# ALIM_MOSFET_1.net
KiCad netlist of a schematic drawn in Altium Designer
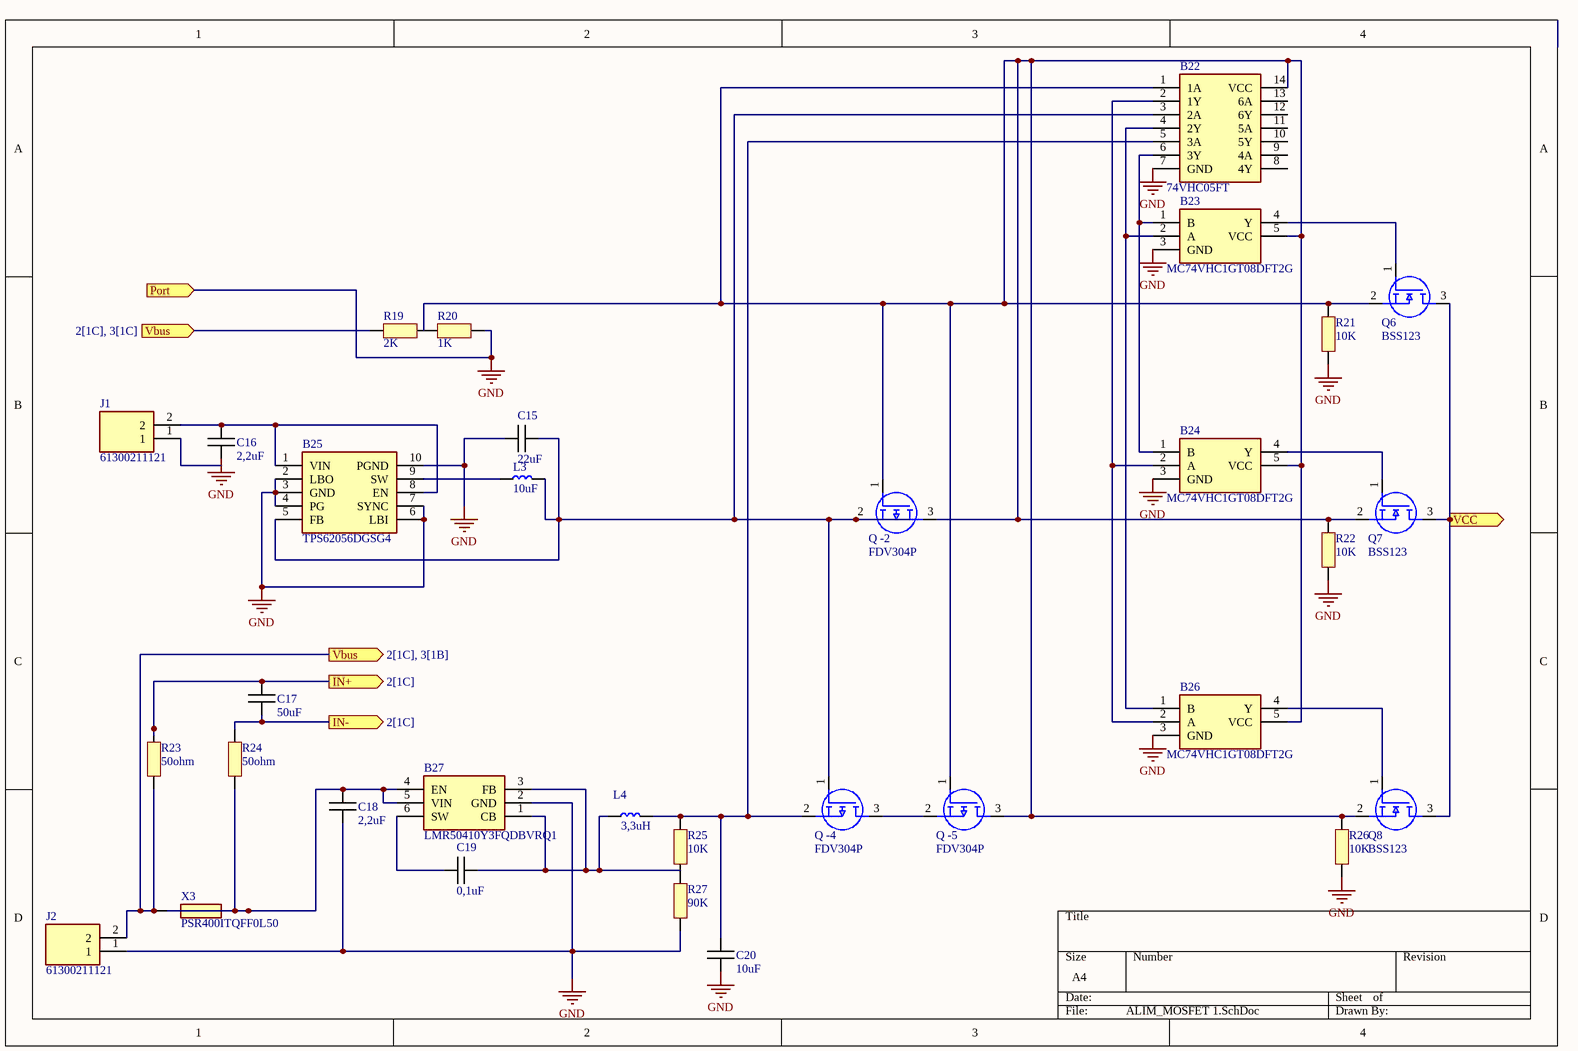
[diagram p0: ALIM_MOSFET 1.SchDoc]

(export (version "E")
  (design (tool "Eeschema 10.0.6"))
  (components
    (comp (ref "B22")
      (value "74VHC05FT")
      (footprint "SOP65P640X120-14N")
      (description "Logic Gates CMOS LOGIC IC INVERTER")
      (fields (field (name "MOUSER PART NUMBER") "757-74VHC05FT"))
      (libsource (lib "SCHLibrary") (part "74VHC05FT"))
    )
    (comp (ref "B23")
      (value "MC74VHC1GT08DFT2G")
      (footprint "SOT65P210X110-5N")
      (description "Single 2-Input AND Gate, TTL Level")
      (libsource (lib "SCHLibrary") (part "MC74VHC1GT08DFT2G"))
    )
    (comp (ref "B24")
      (value "MC74VHC1GT08DFT2G")
      (footprint "SOT65P210X110-5N")
      (description "Single 2-Input AND Gate, TTL Level")
      (libsource (lib "SCHLibrary") (part "MC74VHC1GT08DFT2G"))
    )
    (comp (ref "B25")
      (value "TPS62056DGSG4")
      (footprint "SOP50P490X110-10N")
      (fields (field (name "MOUSER PART NUMBER") "595-TPS62056DGSG4"))
      (libsource (lib "SCHLibrary") (part "TPS62056DGSG4"))
    )
    (comp (ref "B26")
      (value "MC74VHC1GT08DFT2G")
      (footprint "SOT65P210X110-5N")
      (description "Single 2-Input AND Gate, TTL Level")
      (libsource (lib "SCHLibrary") (part "MC74VHC1GT08DFT2G"))
    )
    (comp (ref "B27")
      (value "LMR50410Y3FQDBVRQ1")
      (footprint "SOT95P280X145-6N")
      (fields (field (name "MOUSER PART NUMBER") "595-R50410Y3FQDBVRQ1"))
      (libsource (lib "SCHLibrary") (part "LMR50410Y3FQDBVRQ1"))
    )
    (comp (ref "C15")
      (value "22uF")
      (footprint "CAPC1005X06N")
      (libsource (lib "SCHLibrary") (part "Capacitor"))
    )
    (comp (ref "C16")
      (value "2,2uF")
      (footprint "CAPC1005X06N")
      (libsource (lib "SCHLibrary") (part "Capacitor"))
    )
    (comp (ref "C17")
      (value "50uF")
      (footprint "CAPC1005X06N")
      (libsource (lib "SCHLibrary") (part "Capacitor"))
    )
    (comp (ref "C18")
      (value "2,2uF")
      (footprint "CAPC1005X06N")
      (libsource (lib "SCHLibrary") (part "Capacitor"))
    )
    (comp (ref "C19")
      (value "0,1uF")
      (footprint "CAPC1005X06N")
      (libsource (lib "SCHLibrary") (part "Capacitor"))
    )
    (comp (ref "C20")
      (value "10uF")
      (footprint "CAPC1005X06N")
      (libsource (lib "SCHLibrary") (part "Capacitor"))
    )
    (comp (ref "J1")
      (value "61300211121")
      (footprint "61300211121")
      (description "WURTH ELEKTRONIK - 61300211121 - HEADER, 2.54MM, PIN, THT, VERTICAL, 2WAY")
      (libsource (lib "SCHLibrary") (part "61300211121"))
    )
    (comp (ref "J2")
      (value "61300211121")
      (footprint "61300211121")
      (description "WURTH ELEKTRONIK - 61300211121 - HEADER, 2.54MM, PIN, THT, VERTICAL, 2WAY")
      (libsource (lib "SCHLibrary") (part "61300211121"))
    )
    (comp (ref "L3") (value "10uF") (footprint "LQPC1005X06N") (libsource (lib "SCHLibrary") (part "Bobine")))
    (comp (ref "L4")
      (value "3,3uH")
      (footprint "LQPC1005X06N")
      (libsource (lib "SCHLibrary") (part "Bobine"))
    )
    (comp (ref "Q -2")
      (value "FDV304P")
      (footprint "SOT95P251X112-3N")
      (fields (field (name "MOUSER PART NUMBER") "512-FDV304P"))
      (libsource (lib "SCHLibrary") (part "FDV304P"))
    )
    (comp (ref "Q -4")
      (value "FDV304P")
      (footprint "SOT95P251X112-3N")
      (fields (field (name "MOUSER PART NUMBER") "512-FDV304P"))
      (libsource (lib "SCHLibrary") (part "FDV304P"))
    )
    (comp (ref "Q -5")
      (value "FDV304P")
      (footprint "SOT95P251X112-3N")
      (fields (field (name "MOUSER PART NUMBER") "512-FDV304P"))
      (libsource (lib "SCHLibrary") (part "FDV304P"))
    )
    (comp (ref "Q6")
      (value "BSS123")
      (footprint "BSS123")
      (description "BSS123 N-Channel MOSFET, 170 mA, 100 V PowerTrench, 3-Pin SOT-23 ON Semiconductor")
      (libsource (lib "SCHLibrary") (part "BSS123"))
    )
    (comp (ref "Q7")
      (value "BSS123")
      (footprint "BSS123")
      (description "BSS123 N-Channel MOSFET, 170 mA, 100 V PowerTrench, 3-Pin SOT-23 ON Semiconductor")
      (libsource (lib "SCHLibrary") (part "BSS123"))
    )
    (comp (ref "Q8")
      (value "BSS123")
      (footprint "BSS123")
      (description "BSS123 N-Channel MOSFET, 170 mA, 100 V PowerTrench, 3-Pin SOT-23 ON Semiconductor")
      (libsource (lib "SCHLibrary") (part "BSS123"))
    )
    (comp (ref "R19") (value "2K") (footprint "RESC1005X06N") (libsource (lib "") (part "Resistor_1")))
    (comp (ref "R20") (value "1K") (footprint "RESC1005X06N") (libsource (lib "") (part "Resistor_1")))
    (comp (ref "R21") (value "10K") (footprint "RESC1005X06N") (libsource (lib "") (part "Resistor_2")))
    (comp (ref "R22") (value "10K") (footprint "RESC1005X06N") (libsource (lib "") (part "Resistor_2")))
    (comp (ref "R23")
      (value "50ohm")
      (footprint "RESC1005X06N")
      (libsource (lib "SCHLibrary") (part "Resistor"))
    )
    (comp (ref "R24")
      (value "50ohm")
      (footprint "RESC1005X06N")
      (libsource (lib "SCHLibrary") (part "Resistor"))
    )
    (comp (ref "R25") (value "10K") (footprint "RESC1005X06N") (libsource (lib "") (part "Resistor_2")))
    (comp (ref "R26") (value "10K") (footprint "RESC1005X06N") (libsource (lib "") (part "Resistor_2")))
    (comp (ref "R27") (value "90K") (footprint "RESC1005X06N") (libsource (lib "") (part "Resistor_2")))
    (comp (ref "X3")
      (value "PSR400ITQFF0L50")
      (footprint "RESC10052X200N")
      (fields (field (name "MOUSER PART NUMBER") "755-PSR400ITQFF0L50"))
      (libsource (lib "SCHLibrary") (part "PSR400ITQFF0L50"))
    )
  )
  (nets
    (net (code "1") (name "/IN+") (class "Default")
      (node (ref "C17") (pin "1") (pinfunction "1_1") (pintype "passive"))
      (node (ref "R23") (pin "2") (pinfunction "2_2") (pintype "passive"))
    )
    (net (code "2") (name "/IN-") (class "Default")
      (node (ref "C17") (pin "2") (pinfunction "2_2") (pintype "passive"))
      (node (ref "R24") (pin "2") (pinfunction "2_2") (pintype "passive"))
    )
    (net (code "3") (name "/VCC") (class "Default")
      (node (ref "Q6") (pin "3") (pinfunction "D_3") (pintype "passive"))
      (node (ref "Q7") (pin "3") (pinfunction "D_3") (pintype "passive"))
      (node (ref "Q8") (pin "3") (pinfunction "D_3") (pintype "passive"))
    )
    (net (code "4") (name "/Vbus") (class "Default")
      (node (ref "J2") (pin "2") (pinfunction "2_2") (pintype "passive"))
      (node (ref "R19") (pin "1") (pinfunction "1_1") (pintype "passive"))
      (node (ref "R23") (pin "1") (pinfunction "1_1") (pintype "passive"))
      (node (ref "X3") (pin "1") (pinfunction "1_1") (pintype "passive"))
    )
    (net (code "5") (name "GND") (class "Default")
      (node (ref "B22") (pin "7") (pinfunction "GND_7") (pintype "passive"))
      (node (ref "B23") (pin "3") (pinfunction "GND_3") (pintype "passive"))
      (node (ref "B24") (pin "3") (pinfunction "GND_3") (pintype "passive"))
      (node (ref "B25") (pin "10") (pinfunction "PGND_10") (pintype "passive"))
      (node (ref "B25") (pin "2") (pinfunction "LBO_2") (pintype "passive"))
      (node (ref "B25") (pin "3") (pinfunction "GND_3") (pintype "passive"))
      (node (ref "B25") (pin "4") (pinfunction "PG_4") (pintype "passive"))
      (node (ref "B25") (pin "6") (pinfunction "LBI_6") (pintype "passive"))
      (node (ref "B25") (pin "7") (pinfunction "SYNC_7") (pintype "passive"))
      (node (ref "B26") (pin "3") (pinfunction "GND_3") (pintype "passive"))
      (node (ref "B27") (pin "2") (pinfunction "GND_2") (pintype "passive"))
      (node (ref "C15") (pin "2") (pinfunction "2_2") (pintype "passive"))
      (node (ref "C16") (pin "2") (pinfunction "2_2") (pintype "passive"))
      (node (ref "C18") (pin "2") (pinfunction "2_2") (pintype "passive"))
      (node (ref "C20") (pin "2") (pinfunction "2_2") (pintype "passive"))
      (node (ref "J2") (pin "1") (pinfunction "1_1") (pintype "passive"))
      (node (ref "R20") (pin "2") (pinfunction "2_2") (pintype "passive"))
      (node (ref "R21") (pin "2") (pinfunction "2_2") (pintype "passive"))
      (node (ref "R22") (pin "2") (pinfunction "2_2") (pintype "passive"))
      (node (ref "R26") (pin "2") (pinfunction "2_2") (pintype "passive"))
      (node (ref "R27") (pin "2") (pinfunction "2_2") (pintype "passive"))
    )
    (net (code "6") (name "Net-(B22-1A)") (class "Default")
      (node (ref "B22") (pin "1") (pinfunction "1A_1") (pintype "passive"))
      (node (ref "B22") (pin "14") (pinfunction "VCC_14") (pintype "passive"))
      (node (ref "B23") (pin "5") (pinfunction "VCC_5") (pintype "passive"))
      (node (ref "B24") (pin "5") (pinfunction "VCC_5") (pintype "passive"))
      (node (ref "B26") (pin "5") (pinfunction "VCC_5") (pintype "passive"))
      (node (ref "Q -2") (pin "1") (pinfunction "G_1") (pintype "passive"))
      (node (ref "Q -2") (pin "3") (pinfunction "D_3") (pintype "passive"))
      (node (ref "Q -5") (pin "1") (pinfunction "G_1") (pintype "passive"))
      (node (ref "Q -5") (pin "3") (pinfunction "D_3") (pintype "passive"))
      (node (ref "Q6") (pin "2") (pinfunction "S_2") (pintype "passive"))
      (node (ref "Q7") (pin "2") (pinfunction "S_2") (pintype "passive"))
      (node (ref "Q8") (pin "2") (pinfunction "S_2") (pintype "passive"))
      (node (ref "R20") (pin "1") (pinfunction "1_1") (pintype "passive"))
      (node (ref "R21") (pin "1") (pinfunction "1_1") (pintype "passive"))
      (node (ref "R22") (pin "1") (pinfunction "1_1") (pintype "passive"))
      (node (ref "R26") (pin "1") (pinfunction "1_1") (pintype "passive"))
    )
    (net (code "7") (name "Net-(B22-1Y)") (class "Default")
      (node (ref "B22") (pin "2") (pinfunction "1Y_2") (pintype "passive"))
      (node (ref "B24") (pin "2") (pinfunction "A_2") (pintype "passive"))
      (node (ref "B26") (pin "2") (pinfunction "A_2") (pintype "passive"))
    )
    (net (code "8") (name "Net-(B22-2A)") (class "Default")
      (node (ref "B22") (pin "3") (pinfunction "2A_3") (pintype "passive"))
      (node (ref "B25") (pin "5") (pinfunction "FB_5") (pintype "passive"))
      (node (ref "C15") (pin "1") (pinfunction "1_1") (pintype "passive"))
      (node (ref "L3") (pin "2") (pinfunction "2_2") (pintype "passive"))
      (node (ref "Q -2") (pin "2") (pinfunction "S_2") (pintype "passive"))
      (node (ref "Q -4") (pin "1") (pinfunction "G_1") (pintype "passive"))
    )
    (net (code "9") (name "Net-(B22-2Y)") (class "Default")
      (node (ref "B22") (pin "4") (pinfunction "2Y_4") (pintype "passive"))
      (node (ref "B23") (pin "2") (pinfunction "A_2") (pintype "passive"))
      (node (ref "B26") (pin "1") (pinfunction "B_1") (pintype "passive"))
    )
    (net (code "10") (name "Net-(B22-3A)") (class "Default")
      (node (ref "B22") (pin "5") (pinfunction "3A_5") (pintype "passive"))
      (node (ref "C20") (pin "1") (pinfunction "1_1") (pintype "passive"))
      (node (ref "L4") (pin "2") (pinfunction "2_2") (pintype "passive"))
      (node (ref "Q -4") (pin "2") (pinfunction "S_2") (pintype "passive"))
      (node (ref "R25") (pin "1") (pinfunction "1_1") (pintype "passive"))
    )
    (net (code "11") (name "Net-(B22-3Y)") (class "Default")
      (node (ref "B22") (pin "6") (pinfunction "3Y_6") (pintype "passive"))
      (node (ref "B23") (pin "1") (pinfunction "B_1") (pintype "passive"))
      (node (ref "B24") (pin "1") (pinfunction "B_1") (pintype "passive"))
    )
    (net (code "12") (name "Net-(B23-Y)") (class "Default")
      (node (ref "B23") (pin "4") (pinfunction "Y_4") (pintype "passive"))
      (node (ref "Q6") (pin "1") (pinfunction "G_1") (pintype "passive"))
    )
    (net (code "13") (name "Net-(B24-Y)") (class "Default")
      (node (ref "B24") (pin "4") (pinfunction "Y_4") (pintype "passive"))
      (node (ref "Q7") (pin "1") (pinfunction "G_1") (pintype "passive"))
    )
    (net (code "14") (name "Net-(B25-EN)") (class "Default")
      (node (ref "B25") (pin "1") (pinfunction "VIN_1") (pintype "passive"))
      (node (ref "B25") (pin "8") (pinfunction "EN_8") (pintype "passive"))
      (node (ref "C16") (pin "1") (pinfunction "1_1") (pintype "passive"))
      (node (ref "J1") (pin "2") (pinfunction "2_2") (pintype "passive"))
    )
    (net (code "15") (name "Net-(B25-SW)") (class "Default")
      (node (ref "B25") (pin "9") (pinfunction "SW_9") (pintype "passive"))
      (node (ref "L3") (pin "1") (pinfunction "1_1") (pintype "passive"))
    )
    (net (code "16") (name "Net-(B26-Y)") (class "Default")
      (node (ref "B26") (pin "4") (pinfunction "Y_4") (pintype "passive"))
      (node (ref "Q8") (pin "1") (pinfunction "G_1") (pintype "passive"))
    )
    (net (code "17") (name "Net-(B27-CB)") (class "Default")
      (node (ref "B27") (pin "1") (pinfunction "CB_1") (pintype "passive"))
      (node (ref "B27") (pin "3") (pinfunction "FB_3") (pintype "passive"))
      (node (ref "C19") (pin "1") (pinfunction "1_1") (pintype "passive"))
      (node (ref "L4") (pin "1") (pinfunction "1_1") (pintype "passive"))
      (node (ref "R27") (pin "1") (pinfunction "1_1") (pintype "passive"))
    )
    (net (code "18") (name "Net-(B27-EN)") (class "Default")
      (node (ref "B27") (pin "4") (pinfunction "EN_4") (pintype "passive"))
      (node (ref "B27") (pin "5") (pinfunction "VIN_5") (pintype "passive"))
      (node (ref "C18") (pin "1") (pinfunction "1_1") (pintype "passive"))
      (node (ref "R24") (pin "1") (pinfunction "1_1") (pintype "passive"))
      (node (ref "X3") (pin "2") (pinfunction "2_2") (pintype "passive"))
    )
    (net (code "19") (name "Net-(B27-SW)") (class "Default")
      (node (ref "B27") (pin "6") (pinfunction "SW_6") (pintype "passive"))
      (node (ref "C19") (pin "2") (pinfunction "2_2") (pintype "passive"))
    )
    (net (code "20") (name "Net-(Q -4-D)") (class "Default")
      (node (ref "Q -4") (pin "3") (pinfunction "D_3") (pintype "passive"))
      (node (ref "Q -5") (pin "2") (pinfunction "S_2") (pintype "passive"))
    )
    (net (code "21") (name "unconnected-(B22-4A-Pad9)") (class "Default")
      (node (ref "B22") (pin "9") (pinfunction "4A_9") (pintype "passive"))
    )
    (net (code "22") (name "unconnected-(B22-4Y-Pad8)") (class "Default")
      (node (ref "B22") (pin "8") (pinfunction "4Y_8") (pintype "passive"))
    )
    (net (code "23") (name "unconnected-(B22-5A-Pad11)") (class "Default")
      (node (ref "B22") (pin "11") (pinfunction "5A_11") (pintype "passive"))
    )
    (net (code "24") (name "unconnected-(B22-5Y-Pad10)") (class "Default")
      (node (ref "B22") (pin "10") (pinfunction "5Y_10") (pintype "passive"))
    )
    (net (code "25") (name "unconnected-(B22-6A-Pad13)") (class "Default")
      (node (ref "B22") (pin "13") (pinfunction "6A_13") (pintype "passive"))
    )
    (net (code "26") (name "unconnected-(B22-6Y-Pad12)") (class "Default")
      (node (ref "B22") (pin "12") (pinfunction "6Y_12") (pintype "passive"))
    )
    (net (code "27") (name "unconnected-(J1-Pad1)") (class "Default")
      (node (ref "J1") (pin "1") (pinfunction "1_1") (pintype "passive"))
    )
    (net (code "28") (name "unconnected-(R19-Pad2)") (class "Default")
      (node (ref "R19") (pin "2") (pinfunction "2_2") (pintype "passive"))
    )
    (net (code "29") (name "unconnected-(R25-Pad2)") (class "Default")
      (node (ref "R25") (pin "2") (pinfunction "2_2") (pintype "passive"))
    )
  )
)
